# us__1sch.net
KiCad netlist of a schematic drawn in Altium Designer
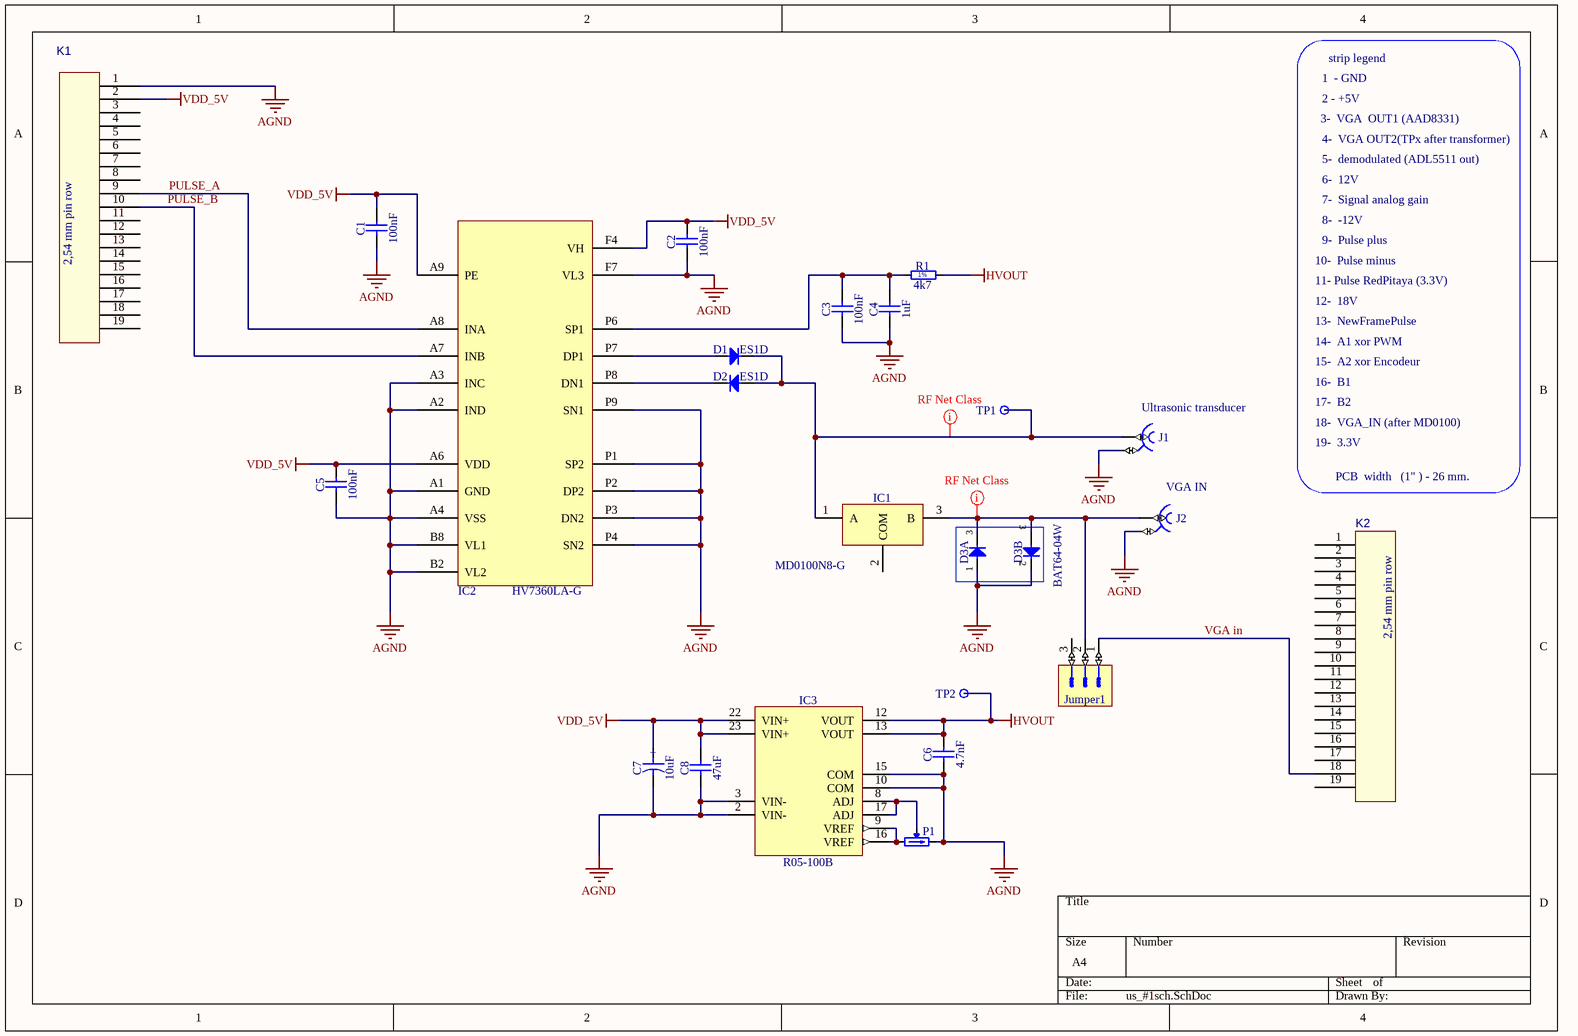
[diagram p0: us_#1sch.SchDoc]

(export (version "E")
  (design (tool "Eeschema 10.0.6"))
  (components
    (comp (ref "C1")
      (value "100nF")
      (footprint "echOpen_ADC_Card:CAPC1608X87N")
      (description "Non-polarised capacitor")
      (fields
        (field (name "PART NUMBER") "CC0603_100NF_50V_10%_X7R")
        (field (name "VOLTAGE") "50V")
        (field (name "AUTHOR") "CERN DEM JLC")
      )
      (libsource (lib "Sof-Capacitors") (part "Capacitor - non polarized"))
    )
    (comp (ref "C2")
      (value "100nF")
      (footprint "echOpen_ADC_Card:CAPC1608X87N")
      (description "Non-polarised capacitor")
      (fields
        (field (name "PART NUMBER") "CC0603_100NF_50V_10%_X7R")
        (field (name "VOLTAGE") "50V")
        (field (name "AUTHOR") "CERN DEM JLC")
      )
      (libsource (lib "Sof-Capacitors") (part "Capacitor - non polarized"))
    )
    (comp (ref "C3")
      (value "100nF")
      (footprint "echOpen_ADC_Card:CAPC1608X87N")
      (description "Non-polarised capacitor")
      (fields
        (field (name "PART NUMBER") "CC0603_100NF_50V_10%_X7R")
        (field (name "VOLTAGE") "50V")
        (field (name "AUTHOR") "CERN DEM JLC")
      )
      (libsource (lib "Sof-Capacitors") (part "Capacitor - non polarized"))
    )
    (comp (ref "C4")
      (value "1uF")
      (footprint "echOpen_ADC_Card:CAPC5650X165N")
      (description "Non-polarised capacitor")
      (fields
        (field (name "PART NUMBER") "CC2220_1UF_200V_10%_X7R")
        (field (name "VOLTAGE") "200V")
        (field (name "AUTHOR") "CERN DEM JLC")
      )
      (libsource (lib "Sof-Capacitors") (part "Capacitor - non polarized"))
    )
    (comp (ref "C5")
      (value "100nF")
      (footprint "echOpen_ADC_Card:CAPC1608X87N")
      (description "Non-polarised capacitor")
      (fields
        (field (name "PART NUMBER") "CC0603_100NF_50V_10%_X7R")
        (field (name "VOLTAGE") "50V")
        (field (name "AUTHOR") "CERN DEM JLC")
      )
      (libsource (lib "Sof-Capacitors") (part "Capacitor - non polarized"))
    )
    (comp (ref "C6")
      (value "4.7nF")
      (footprint "echOpen_ADC_Card:CAPC2012X110N")
      (description "Non-polarised capacitor")
      (fields
        (field (name "PART NUMBER") "CC0805_4.7NF_250V_10%_X7R")
        (field (name "VOLTAGE") "250V")
        (field (name "AUTHOR") "S. Jafar")
      )
      (libsource (lib "Sof-Capacitors") (part "Capacitor - non polarized"))
    )
    (comp (ref "C7")
      (value "10uF")
      (footprint "echOpen_ADC_Card:CAPMP3528X210N")
      (description "Polarised capacitor")
      (fields
        (field (name "PART NUMBER") "CTE3528-21_10UF_16V_10%_LESR0800")
        (field (name "VOLTAGE") "16V")
        (field (name "AUTHOR") "CERN DEM JLC")
      )
      (libsource (lib "Sof-Capacitors") (part "Capacitor - polarized"))
    )
    (comp (ref "C8")
      (value "47uF")
      (footprint "echOpen_ADC_Card:CAPC3216X180N")
      (description "Non-polarised capacitor")
      (fields
        (field (name "PART NUMBER") "CC1206_47UF_25V_20%_X5R")
        (field (name "VOLTAGE") "25V")
        (field (name "AUTHOR") "CERN DEM JLC")
      )
      (libsource (lib "Sof-Capacitors") (part "Capacitor - non polarized"))
    )
    (comp (ref "D1")
      (value "ES1D")
      (footprint "echOpen_ADC_Card:DIOM5027X244N")
      (description "Diode")
      (fields
        (field (name "VOLTAGE") "200V")
        (field (name "POWER") "1A")
        (field (name "AUTHOR") "CERN DEM JLC")
      )
      (libsource (lib "Sof-ICs And Semiconductors") (part "Diode"))
    )
    (comp (ref "D2")
      (value "ES1D")
      (footprint "echOpen_ADC_Card:DIOM5027X244N")
      (description "Diode")
      (fields
        (field (name "VOLTAGE") "200V")
        (field (name "POWER") "1A")
        (field (name "AUTHOR") "CERN DEM JLC")
      )
      (libsource (lib "Sof-ICs And Semiconductors") (part "Diode"))
    )
    (comp (ref "D3")
      (value "BAT64-04W")
      (footprint "echOpen_ADC_Card:SOT65P210X100-3N")
      (description "Serial Diode")
      (fields
        (field (name "VOLTAGE") "40V")
        (field (name "POWER") "250mW")
        (field (name "AUTHOR") "CERN DEM JMW")
      )
      (libsource (lib "Sof-ICs And Semiconductors") (part "Diode x2 A1C3_A3C2"))
    )
    (comp (ref "IC1")
      (value "MD0100N8-G")
      (footprint "echOpen_ADC_Card:SOT89")
      (description "3-Ultra-Sound HV Switch 1=A 2=COM 3=B")
      (fields (field (name "MANUFACTURER") "Supertex inc.") (field (name "AUTHOR") "S. Jafar"))
      (libsource (lib "Sof-ICs And Semiconductors") (part "MD0100"))
    )
    (comp (ref "IC2")
      (value "HV7360LA-G")
      (footprint "echOpen_ADC_Card:HV7360")
      (fields (field (name "MANUFACTURER") "Supertex inc.") (field (name "AUTHOR") "S. Jafar"))
      (libsource (lib "Sof-ICs And Semiconductors") (part "HV7360"))
    )
    (comp (ref "IC3")
      (value "R05-100B")
      (footprint "echOpen_ADC_Card:PWS_RECOM_R05-100B")
      (description "Power Supply")
      (fields (field (name "MANUFACTURER") "RECOM POWER") (field (name "AUTHOR") "S. Jafar"))
      (libsource (lib "echOpen_ADC_Card") (part "PWS_RECOM_R05-100B"))
    )
    (comp (ref "J1")
      (value "SMA")
      (footprint "echOpen_ADC_Card:AMPHENOL_132357-11")
      (fields
        (field (name "PART NUMBER") "AMPHENOL_132357-11")
        (field (name "MANUFACTURER") "AMPHENOL")
        (field (name "MANUFACTURER PART NUMBER") "132357-11")
        (field (name "AUTHOR") "CERN DEM JLC")
      )
      (libsource (lib "Sof-Connectors") (part "Coax_1Female_1Shield"))
    )
    (comp (ref "J2")
      (value "SMA")
      (footprint "echOpen_ADC_Card:AMPHENOL_132357-11")
      (fields
        (field (name "PART NUMBER") "AMPHENOL_132357-11")
        (field (name "MANUFACTURER") "AMPHENOL")
        (field (name "MANUFACTURER PART NUMBER") "132357-11")
        (field (name "AUTHOR") "CERN DEM JLC")
      )
      (libsource (lib "Sof-Connectors") (part "Coax_1Female_1Shield"))
    )
    (comp (ref "Jumper1")
      (value "~")
      (footprint "echOpen_ADC_Card:SULLINS_GRPB031VWVN")
      (description "Connector 3 Male")
      (fields
        (field (name "PART NUMBER") "SULLINS_GRPB031VWVN")
        (field (name "MANUFACTURER") "SULLINS")
        (field (name "AUTHOR") "S. Jafar")
      )
      (libsource (lib "echOpen_ADC_Card") (part "Connector 3 Male"))
    )
    (comp (ref "K1")
      (value "PLS_2.54mm-19")
      (footprint "PLS_2.54mm-19")
      (libsource (lib "alt_vovan") (part "PLS_2.54mm-19"))
    )
    (comp (ref "K2")
      (value "PLS_2.54mm-19")
      (footprint "PLS_2.54mm-19")
      (libsource (lib "") (part "PLS_2.54mm-19_1"))
    )
    (comp (ref "P1")
      (value "5k")
      (footprint "echOpen_ADC_Card:TRIM_BOURNS_3223W")
      (description "Trimming Potentiometer")
      (fields
        (field (name "PART NUMBER") "TRIM_11T_5K_BOURNS_3223W-1-502E")
        (field (name "POWER") "0.125W")
        (field (name "AUTHOR") "CERN DEM JLC")
      )
      (libsource (lib "Sof-Resistors") (part "Trimming Potentiometer"))
    )
    (comp (ref "R1")
      (value "4k7")
      (footprint "echOpen_ADC_Card:RESC3216X65N")
      (description "Resistor - 1%")
      (fields
        (field (name "PART NUMBER") "R1206_4K7_1%_0.25W_100PPM")
        (field (name "POWER") "0.25W")
        (field (name "AUTHOR") "CERN DEM JLC")
      )
      (libsource (lib "Sof-Resistors") (part "Resistor - 1%"))
    )
    (comp (ref "TP1")
      (value "Test Point")
      (footprint "echOpen_ADC_Card:NICOMATIC_C12000B")
      (fields
        (field (name "PART NUMBER") "NICOMATIC_C12000B")
        (field (name "MANUFACTURER") "NICOMATIC")
        (field (name "MANUFACTURER PART NUMBER") "C12000B")
        (field (name "AUTHOR") "CERN DEM JLC")
      )
      (libsource (lib "Sof-Connectors") (part "Test Point"))
    )
    (comp (ref "TP2")
      (value "Test Point")
      (footprint "echOpen_ADC_Card:NICOMATIC_C12000B")
      (fields
        (field (name "PART NUMBER") "NICOMATIC_C12000B")
        (field (name "MANUFACTURER") "NICOMATIC")
        (field (name "MANUFACTURER PART NUMBER") "C12000B")
        (field (name "AUTHOR") "CERN DEM JLC")
      )
      (libsource (lib "Sof-Connectors") (part "Test Point"))
    )
  )
  (nets
    (net (code "1") (name "/PULSE_A") (class "Default")
      (node (ref "IC2") (pin "A8") (pinfunction "INA_A8") (pintype "passive"))
      (node (ref "K1") (pin "9") (pinfunction "9_9") (pintype "passive"))
    )
    (net (code "2") (name "/PULSE_B") (class "Default")
      (node (ref "IC2") (pin "A7") (pinfunction "INB_A7") (pintype "passive"))
      (node (ref "K1") (pin "10") (pinfunction "10_10") (pintype "passive"))
    )
    (net (code "3") (name "/VGA in") (class "Default")
      (node (ref "Jumper1") (pin "1") (pinfunction "1_1") (pintype "bidirectional"))
      (node (ref "K2") (pin "18") (pinfunction "18_18") (pintype "passive"))
    )
    (net (code "4") (name "AGND") (class "Default")
      (node (ref "C1") (pin "1") (pinfunction "1_1") (pintype "passive"))
      (node (ref "C2") (pin "1") (pinfunction "1_1") (pintype "passive"))
      (node (ref "C3") (pin "1") (pinfunction "1_1") (pintype "passive"))
      (node (ref "C4") (pin "1") (pinfunction "1_1") (pintype "passive"))
      (node (ref "C5") (pin "1") (pinfunction "1_1") (pintype "passive"))
      (node (ref "C6") (pin "1") (pinfunction "1_1") (pintype "passive"))
      (node (ref "C7") (pin "2") (pinfunction "2_2") (pintype "passive"))
      (node (ref "C8") (pin "1") (pinfunction "1_1") (pintype "passive"))
      (node (ref "D3") (pin "1") (pinfunction "A_1") (pintype "passive"))
      (node (ref "D3") (pin "2") (pinfunction "C_2") (pintype "passive"))
      (node (ref "IC2") (pin "A1") (pinfunction "GND_A1") (pintype "passive"))
      (node (ref "IC2") (pin "A2") (pinfunction "IND_A2") (pintype "passive"))
      (node (ref "IC2") (pin "A3") (pinfunction "INC_A3") (pintype "passive"))
      (node (ref "IC2") (pin "A4") (pinfunction "VSS_A4") (pintype "passive"))
      (node (ref "IC2") (pin "B2") (pinfunction "VL2_B2") (pintype "passive"))
      (node (ref "IC2") (pin "B8") (pinfunction "VL1_B8") (pintype "passive"))
      (node (ref "IC2") (pin "F7") (pinfunction "VL3_F7") (pintype "passive"))
      (node (ref "IC2") (pin "P1") (pinfunction "SP2_P1") (pintype "passive"))
      (node (ref "IC2") (pin "P2") (pinfunction "DP2_P2") (pintype "passive"))
      (node (ref "IC2") (pin "P3") (pinfunction "DN2_P3") (pintype "passive"))
      (node (ref "IC2") (pin "P4") (pinfunction "SN2_P4") (pintype "passive"))
      (node (ref "IC2") (pin "P9") (pinfunction "SN1_P9") (pintype "passive"))
      (node (ref "IC3") (pin "10") (pinfunction "COM_10") (pintype "power_in"))
      (node (ref "IC3") (pin "15") (pinfunction "COM_15") (pintype "power_in"))
      (node (ref "IC3") (pin "2") (pinfunction "VIN-_2") (pintype "passive"))
      (node (ref "IC3") (pin "3") (pinfunction "VIN-_3") (pintype "passive"))
      (node (ref "J1") (pin "2") (pinfunction "2_2") (pintype "bidirectional"))
      (node (ref "J2") (pin "2") (pinfunction "2_2") (pintype "bidirectional"))
      (node (ref "K1") (pin "1") (pinfunction "1_1") (pintype "passive"))
      (node (ref "P1") (pin "3") (pinfunction "CW_3") (pintype "passive"))
    )
    (net (code "5") (name "HVOUT") (class "Default")
      (node (ref "C6") (pin "2") (pinfunction "2_2") (pintype "passive"))
      (node (ref "IC3") (pin "12") (pinfunction "VOUT_12") (pintype "power_in"))
      (node (ref "IC3") (pin "13") (pinfunction "VOUT_13") (pintype "power_in"))
      (node (ref "R1") (pin "2") (pinfunction "2_2") (pintype "passive"))
      (node (ref "TP2") (pin "1") (pinfunction "1_1") (pintype "bidirectional"))
    )
    (net (code "6") (name "Net-(D1-A)") (class "Default")
      (node (ref "D1") (pin "2") (pinfunction "A_2") (pintype "passive"))
      (node (ref "IC2") (pin "P7") (pinfunction "DP1_P7") (pintype "passive"))
    )
    (net (code "7") (name "Net-(D1-C)") (class "Default")
      (node (ref "D1") (pin "1") (pinfunction "C_1") (pintype "passive"))
      (node (ref "D2") (pin "2") (pinfunction "A_2") (pintype "passive"))
      (node (ref "IC1") (pin "1") (pinfunction "A_1") (pintype "passive"))
      (node (ref "J1") (pin "1") (pinfunction "1_1") (pintype "bidirectional"))
      (node (ref "TP1") (pin "1") (pinfunction "1_1") (pintype "bidirectional"))
    )
    (net (code "8") (name "Net-(D2-C)") (class "Default")
      (node (ref "D2") (pin "1") (pinfunction "C_1") (pintype "passive"))
      (node (ref "IC2") (pin "P8") (pinfunction "DN1_P8") (pintype "passive"))
    )
    (net (code "9") (name "Net-(D3A-COMAC)") (class "Default")
      (node (ref "D3") (pin "3") (pinfunction "COMAC_3") (pintype "passive"))
      (node (ref "IC1") (pin "3") (pinfunction "B_3") (pintype "passive"))
      (node (ref "J2") (pin "1") (pinfunction "1_1") (pintype "bidirectional"))
      (node (ref "Jumper1") (pin "2") (pinfunction "2_2") (pintype "bidirectional"))
    )
    (net (code "10") (name "Net-(IC2-SP1)") (class "Default")
      (node (ref "C3") (pin "2") (pinfunction "2_2") (pintype "passive"))
      (node (ref "C4") (pin "2") (pinfunction "2_2") (pintype "passive"))
      (node (ref "IC2") (pin "P6") (pinfunction "SP1_P6") (pintype "passive"))
      (node (ref "R1") (pin "1") (pinfunction "1_1") (pintype "passive"))
    )
    (net (code "11") (name "Net-(P1-CCW)") (class "Default")
      (node (ref "IC3") (pin "16") (pinfunction "VREF_16") (pintype "output"))
      (node (ref "IC3") (pin "9") (pinfunction "VREF_9") (pintype "output"))
      (node (ref "P1") (pin "1") (pinfunction "CCW_1") (pintype "passive"))
    )
    (net (code "12") (name "Net-(P1-W)") (class "Default")
      (node (ref "IC3") (pin "17") (pinfunction "ADJ_17") (pintype "passive"))
      (node (ref "IC3") (pin "8") (pinfunction "ADJ_8") (pintype "passive"))
      (node (ref "P1") (pin "2") (pinfunction "W_2") (pintype "passive"))
    )
    (net (code "13") (name "VDD_5V") (class "Default")
      (node (ref "C1") (pin "2") (pinfunction "2_2") (pintype "passive"))
      (node (ref "C2") (pin "2") (pinfunction "2_2") (pintype "passive"))
      (node (ref "C5") (pin "2") (pinfunction "2_2") (pintype "passive"))
      (node (ref "C7") (pin "1") (pinfunction "1_1") (pintype "passive"))
      (node (ref "C8") (pin "2") (pinfunction "2_2") (pintype "passive"))
      (node (ref "IC2") (pin "A6") (pinfunction "VDD_A6") (pintype "passive"))
      (node (ref "IC2") (pin "A9") (pinfunction "PE_A9") (pintype "passive"))
      (node (ref "IC2") (pin "F4") (pinfunction "VH_F4") (pintype "passive"))
      (node (ref "IC3") (pin "22") (pinfunction "VIN+_22") (pintype "power_in"))
      (node (ref "IC3") (pin "23") (pinfunction "VIN+_23") (pintype "power_in"))
      (node (ref "K1") (pin "2") (pinfunction "2_2") (pintype "passive"))
    )
    (net (code "14") (name "unconnected-(IC1-COM-Pad2)") (class "Default")
      (node (ref "IC1") (pin "2") (pinfunction "COM_2") (pintype "passive"))
    )
    (net (code "15") (name "unconnected-(Jumper1-Pad3)") (class "Default")
      (node (ref "Jumper1") (pin "3") (pinfunction "3_3") (pintype "bidirectional"))
    )
    (net (code "16") (name "unconnected-(K1-Pad3)") (class "Default")
      (node (ref "K1") (pin "3") (pinfunction "3_3") (pintype "passive"))
    )
    (net (code "17") (name "unconnected-(K1-Pad4)") (class "Default")
      (node (ref "K1") (pin "4") (pinfunction "4_4") (pintype "passive"))
    )
    (net (code "18") (name "unconnected-(K1-Pad5)") (class "Default")
      (node (ref "K1") (pin "5") (pinfunction "5_5") (pintype "passive"))
    )
    (net (code "19") (name "unconnected-(K1-Pad6)") (class "Default")
      (node (ref "K1") (pin "6") (pinfunction "6_6") (pintype "passive"))
    )
    (net (code "20") (name "unconnected-(K1-Pad7)") (class "Default")
      (node (ref "K1") (pin "7") (pinfunction "7_7") (pintype "passive"))
    )
    (net (code "21") (name "unconnected-(K1-Pad8)") (class "Default")
      (node (ref "K1") (pin "8") (pinfunction "8_8") (pintype "passive"))
    )
    (net (code "22") (name "unconnected-(K1-Pad11)") (class "Default")
      (node (ref "K1") (pin "11") (pinfunction "11_11") (pintype "passive"))
    )
    (net (code "23") (name "unconnected-(K1-Pad12)") (class "Default")
      (node (ref "K1") (pin "12") (pinfunction "12_12") (pintype "passive"))
    )
    (net (code "24") (name "unconnected-(K1-Pad13)") (class "Default")
      (node (ref "K1") (pin "13") (pinfunction "13_13") (pintype "passive"))
    )
    (net (code "25") (name "unconnected-(K1-Pad14)") (class "Default")
      (node (ref "K1") (pin "14") (pinfunction "14_14") (pintype "passive"))
    )
    (net (code "26") (name "unconnected-(K1-Pad15)") (class "Default")
      (node (ref "K1") (pin "15") (pinfunction "15_15") (pintype "passive"))
    )
    (net (code "27") (name "unconnected-(K1-Pad16)") (class "Default")
      (node (ref "K1") (pin "16") (pinfunction "16_16") (pintype "passive"))
    )
    (net (code "28") (name "unconnected-(K1-Pad17)") (class "Default")
      (node (ref "K1") (pin "17") (pinfunction "17_17") (pintype "passive"))
    )
    (net (code "29") (name "unconnected-(K1-Pad18)") (class "Default")
      (node (ref "K1") (pin "18") (pinfunction "18_18") (pintype "passive"))
    )
    (net (code "30") (name "unconnected-(K1-Pad19)") (class "Default")
      (node (ref "K1") (pin "19") (pinfunction "19_19") (pintype "passive"))
    )
    (net (code "31") (name "unconnected-(K2-Pad1)") (class "Default")
      (node (ref "K2") (pin "1") (pinfunction "1_1") (pintype "passive"))
    )
    (net (code "32") (name "unconnected-(K2-Pad2)") (class "Default")
      (node (ref "K2") (pin "2") (pinfunction "2_2") (pintype "passive"))
    )
    (net (code "33") (name "unconnected-(K2-Pad3)") (class "Default")
      (node (ref "K2") (pin "3") (pinfunction "3_3") (pintype "passive"))
    )
    (net (code "34") (name "unconnected-(K2-Pad4)") (class "Default")
      (node (ref "K2") (pin "4") (pinfunction "4_4") (pintype "passive"))
    )
    (net (code "35") (name "unconnected-(K2-Pad5)") (class "Default")
      (node (ref "K2") (pin "5") (pinfunction "5_5") (pintype "passive"))
    )
    (net (code "36") (name "unconnected-(K2-Pad6)") (class "Default")
      (node (ref "K2") (pin "6") (pinfunction "6_6") (pintype "passive"))
    )
    (net (code "37") (name "unconnected-(K2-Pad7)") (class "Default")
      (node (ref "K2") (pin "7") (pinfunction "7_7") (pintype "passive"))
    )
    (net (code "38") (name "unconnected-(K2-Pad8)") (class "Default")
      (node (ref "K2") (pin "8") (pinfunction "8_8") (pintype "passive"))
    )
    (net (code "39") (name "unconnected-(K2-Pad9)") (class "Default")
      (node (ref "K2") (pin "9") (pinfunction "9_9") (pintype "passive"))
    )
    (net (code "40") (name "unconnected-(K2-Pad10)") (class "Default")
      (node (ref "K2") (pin "10") (pinfunction "10_10") (pintype "passive"))
    )
    (net (code "41") (name "unconnected-(K2-Pad11)") (class "Default")
      (node (ref "K2") (pin "11") (pinfunction "11_11") (pintype "passive"))
    )
    (net (code "42") (name "unconnected-(K2-Pad12)") (class "Default")
      (node (ref "K2") (pin "12") (pinfunction "12_12") (pintype "passive"))
    )
    (net (code "43") (name "unconnected-(K2-Pad13)") (class "Default")
      (node (ref "K2") (pin "13") (pinfunction "13_13") (pintype "passive"))
    )
    (net (code "44") (name "unconnected-(K2-Pad14)") (class "Default")
      (node (ref "K2") (pin "14") (pinfunction "14_14") (pintype "passive"))
    )
    (net (code "45") (name "unconnected-(K2-Pad15)") (class "Default")
      (node (ref "K2") (pin "15") (pinfunction "15_15") (pintype "passive"))
    )
    (net (code "46") (name "unconnected-(K2-Pad16)") (class "Default")
      (node (ref "K2") (pin "16") (pinfunction "16_16") (pintype "passive"))
    )
    (net (code "47") (name "unconnected-(K2-Pad17)") (class "Default")
      (node (ref "K2") (pin "17") (pinfunction "17_17") (pintype "passive"))
    )
    (net (code "48") (name "unconnected-(K2-Pad19)") (class "Default")
      (node (ref "K2") (pin "19") (pinfunction "19_19") (pintype "passive"))
    )
  )
)
